# Power.net
KiCad netlist of a schematic drawn in Altium Designer
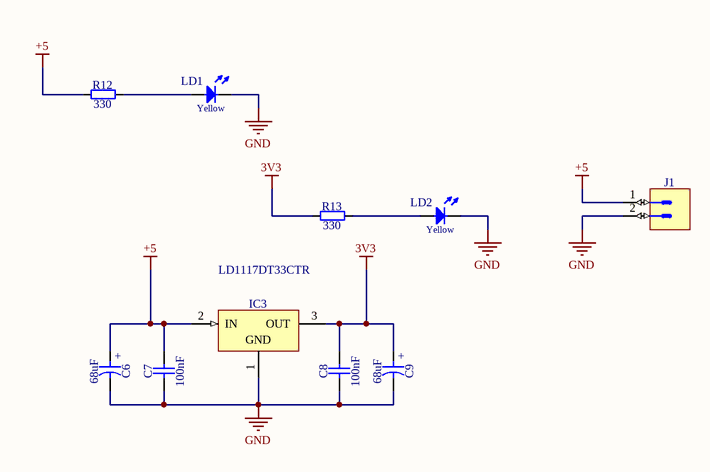
[diagram p0: Power.SchDoc]

(export (version "E")
  (design (tool "Eeschema 10.0.6"))
  (components
    (comp (ref "C6")
      (value "68uF")
      (footprint "CAPAE660X540N")
      (description "Polarised capacitor")
      (fields
        (field (name "PART NUMBER") "CAE660-540_220UF_6.3V_20%")
        (field (name "VOLTAGE") "6.3V")
        (field (name "AUTHOR") "CERN DEM JLC")
      )
      (libsource (lib "Capacitors") (part "Capacitor - polarized"))
    )
    (comp (ref "C7")
      (value "100nF")
      (footprint "CAPC2012X135N")
      (description "Non-polarised capacitor")
      (fields
        (field (name "PART NUMBER") "CC0805_100NF_50V_10%_X7R")
        (field (name "VOLTAGE") "50V")
        (field (name "AUTHOR") "CERN DEM JLC")
      )
      (libsource (lib "Capacitors") (part "Capacitor - non polarized"))
    )
    (comp (ref "C8")
      (value "100nF")
      (footprint "CAPC2012X135N")
      (description "Non-polarised capacitor")
      (fields
        (field (name "PART NUMBER") "CC0805_100NF_50V_10%_X7R")
        (field (name "VOLTAGE") "50V")
        (field (name "AUTHOR") "CERN DEM JLC")
      )
      (libsource (lib "Capacitors") (part "Capacitor - non polarized"))
    )
    (comp (ref "C9")
      (value "68uF")
      (footprint "CAPAE660X540N")
      (description "Polarised capacitor")
      (fields
        (field (name "PART NUMBER") "CAE660-540_220UF_6.3V_20%")
        (field (name "VOLTAGE") "6.3V")
        (field (name "AUTHOR") "CERN DEM JLC")
      )
      (libsource (lib "Capacitors") (part "Capacitor - polarized"))
    )
    (comp (ref "IC3")
      (value "LD1117DT33CTR")
      (footprint "TO228P972X240-3N-R540X510")
      (description "3-Terminal Regulator 1=GND 2=IN 3=OUT")
      (fields (field (name "MANUFACTURER") "ST MICROELECTRONICS") (field (name "AUTHOR") "CERN DEM JLC"))
      (libsource (lib "ICs And Semiconductors") (part "REG3 1GND-2IN-3OUT"))
    )
    (comp (ref "J1")
      (value "Header 2")
      (footprint "JST_B2B-XH-A(LF)(SN)")
      (description "Connector 2 Male")
      (fields
        (field (name "PART NUMBER") "JST_B2B-XH-A(LF)(SN)")
        (field (name "MANUFACTURER") "JST (JAPAN SOLDERLESS TERMINALS)")
        (field (name "AUTHOR") "CERN DEM JLC")
      )
      (libsource (lib "Connectors") (part "Connector 2 Male"))
    )
    (comp (ref "LD1")
      (value "Yellow")
      (footprint "LED_3MM_YELLOW_1C-2A")
      (description "LED Yellow 1C 2A")
      (fields
        (field (name "PART NUMBER") "LED_AVAGO_HLMP-1719")
        (field (name "MANUFACTURER") "AVAGO TECHNOLOGIES")
        (field (name "AUTHOR") "CERN DEM JLC")
      )
      (libsource (lib "ICs And Semiconductors") (part "LED Yellow 1C 2A"))
    )
    (comp (ref "LD2")
      (value "Yellow")
      (footprint "LED_3MM_YELLOW_1C-2A")
      (description "LED Yellow 1C 2A")
      (fields
        (field (name "PART NUMBER") "LED_AVAGO_HLMP-1719")
        (field (name "MANUFACTURER") "AVAGO TECHNOLOGIES")
        (field (name "AUTHOR") "CERN DEM JLC")
      )
      (libsource (lib "ICs And Semiconductors") (part "LED Yellow 1C 2A"))
    )
    (comp (ref "R12")
      (value "330")
      (footprint "RESC2012X60N")
      (description "Resistor - 1%")
      (fields
        (field (name "PART NUMBER") "R0805_24K_1%_0.125W_100PPM")
        (field (name "POWER") "0.125W")
        (field (name "AUTHOR") "CERN DEM JLC")
      )
      (libsource (lib "Resistors") (part "Resistor - 1%"))
    )
    (comp (ref "R13")
      (value "330")
      (footprint "RESC2012X60N")
      (description "Resistor - 1%")
      (fields
        (field (name "PART NUMBER") "R0805_24K_1%_0.125W_100PPM")
        (field (name "POWER") "0.125W")
        (field (name "AUTHOR") "CERN DEM JLC")
      )
      (libsource (lib "Resistors") (part "Resistor - 1%"))
    )
  )
  (nets
    (net (code "1") (name "+5") (class "Default")
      (node (ref "C6") (pin "1") (pinfunction "1_1") (pintype "passive"))
      (node (ref "C7") (pin "2") (pinfunction "2_2") (pintype "passive"))
      (node (ref "IC3") (pin "2") (pinfunction "IN_2") (pintype "input"))
      (node (ref "J1") (pin "1") (pinfunction "1_1") (pintype "bidirectional"))
      (node (ref "R12") (pin "1") (pinfunction "1_1") (pintype "passive"))
    )
    (net (code "2") (name "3V3") (class "Default")
      (node (ref "C8") (pin "2") (pinfunction "2_2") (pintype "passive"))
      (node (ref "C9") (pin "1") (pinfunction "1_1") (pintype "passive"))
      (node (ref "IC3") (pin "3") (pinfunction "OUT_3") (pintype "power_in"))
      (node (ref "R13") (pin "1") (pinfunction "1_1") (pintype "passive"))
    )
    (net (code "3") (name "GND") (class "Default")
      (node (ref "C6") (pin "2") (pinfunction "2_2") (pintype "passive"))
      (node (ref "C7") (pin "1") (pinfunction "1_1") (pintype "passive"))
      (node (ref "C8") (pin "1") (pinfunction "1_1") (pintype "passive"))
      (node (ref "C9") (pin "2") (pinfunction "2_2") (pintype "passive"))
      (node (ref "IC3") (pin "1") (pinfunction "GND_1") (pintype "power_in"))
      (node (ref "J1") (pin "2") (pinfunction "2_2") (pintype "bidirectional"))
      (node (ref "LD1") (pin "1") (pinfunction "C_1") (pintype "passive"))
      (node (ref "LD2") (pin "1") (pinfunction "C_1") (pintype "passive"))
    )
    (net (code "4") (name "Net-(LD1-A)") (class "Default")
      (node (ref "LD1") (pin "2") (pinfunction "A_2") (pintype "passive"))
      (node (ref "R12") (pin "2") (pinfunction "2_2") (pintype "passive"))
    )
    (net (code "5") (name "Net-(LD2-A)") (class "Default")
      (node (ref "LD2") (pin "2") (pinfunction "A_2") (pintype "passive"))
      (node (ref "R13") (pin "2") (pinfunction "2_2") (pintype "passive"))
    )
  )
)
